# Gimbal_Controller_Board.net
KiCad netlist of a schematic drawn in EAGLE
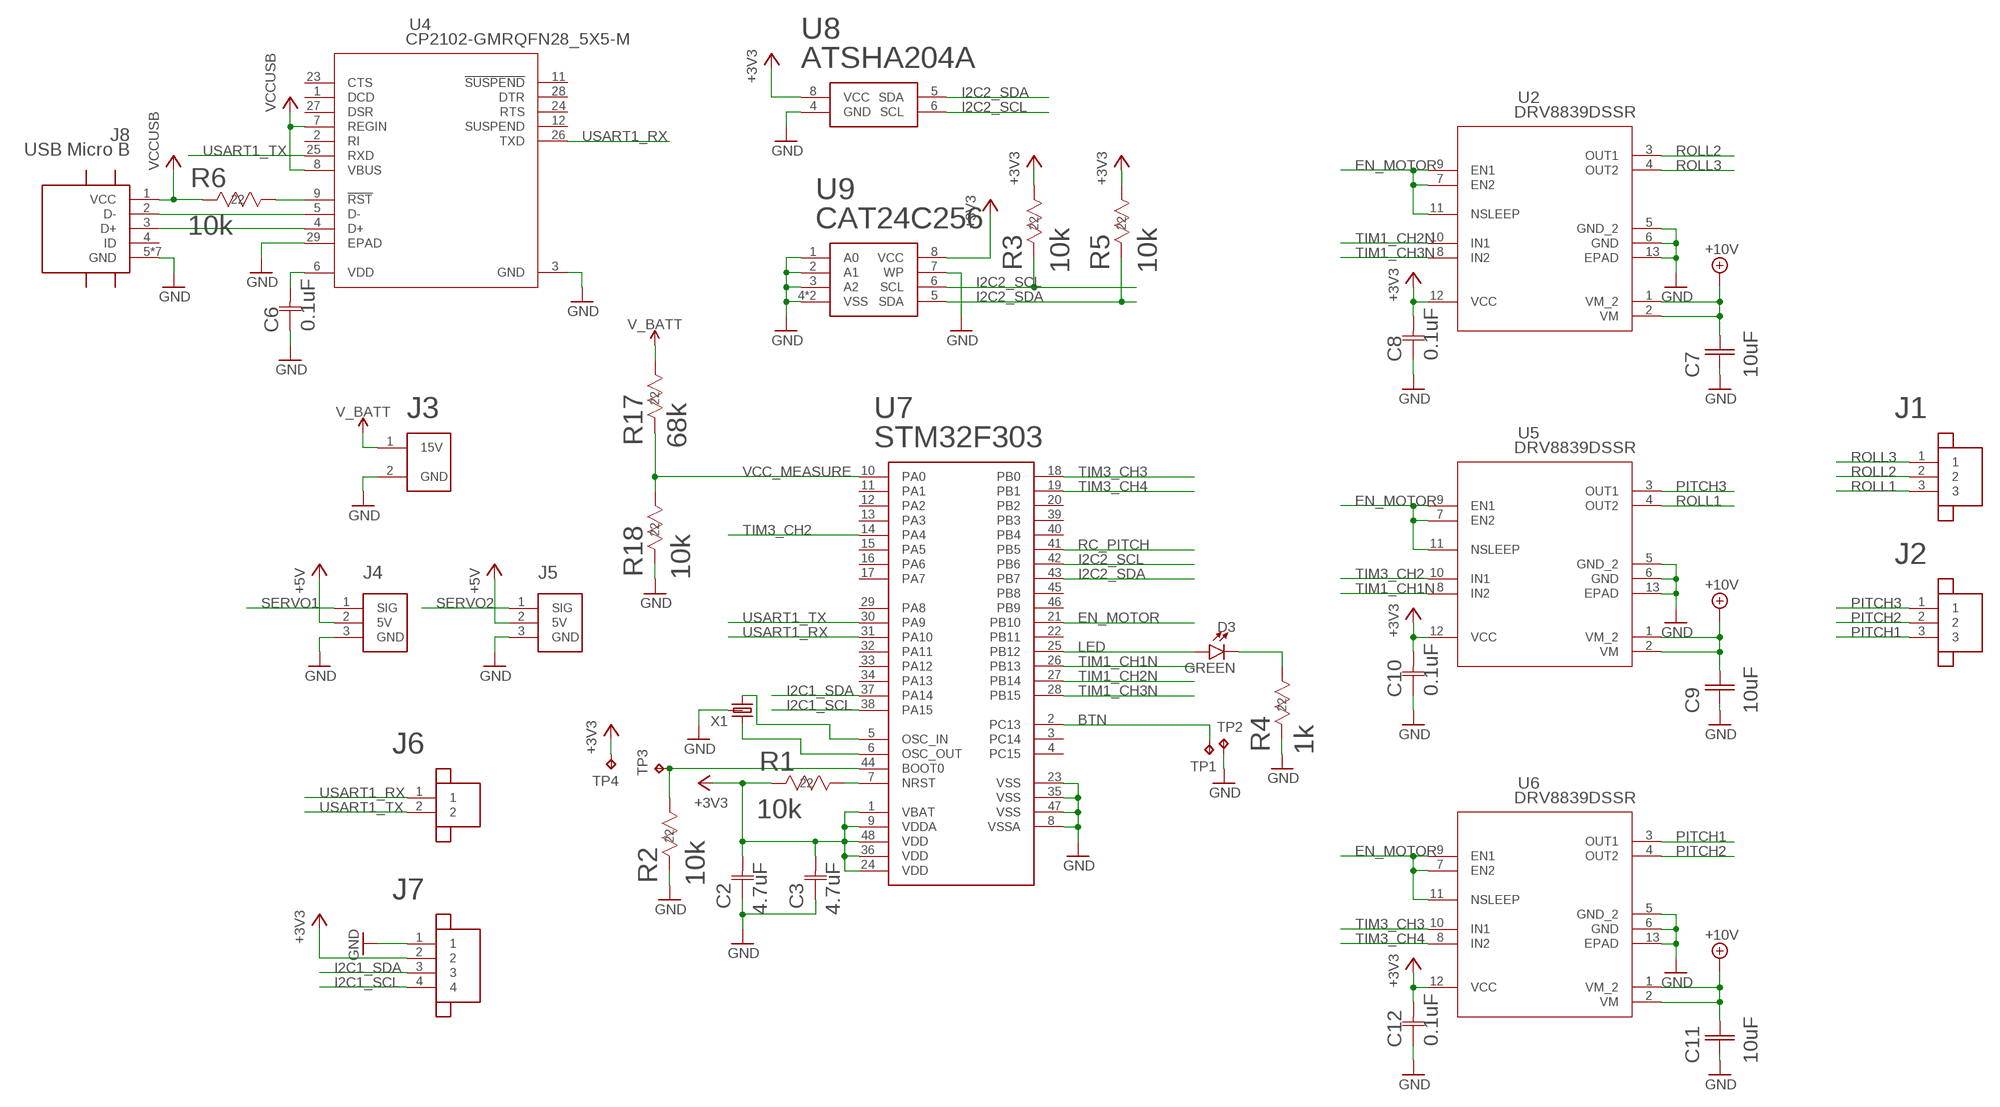
[diagram p0: schematic, sheet 1]
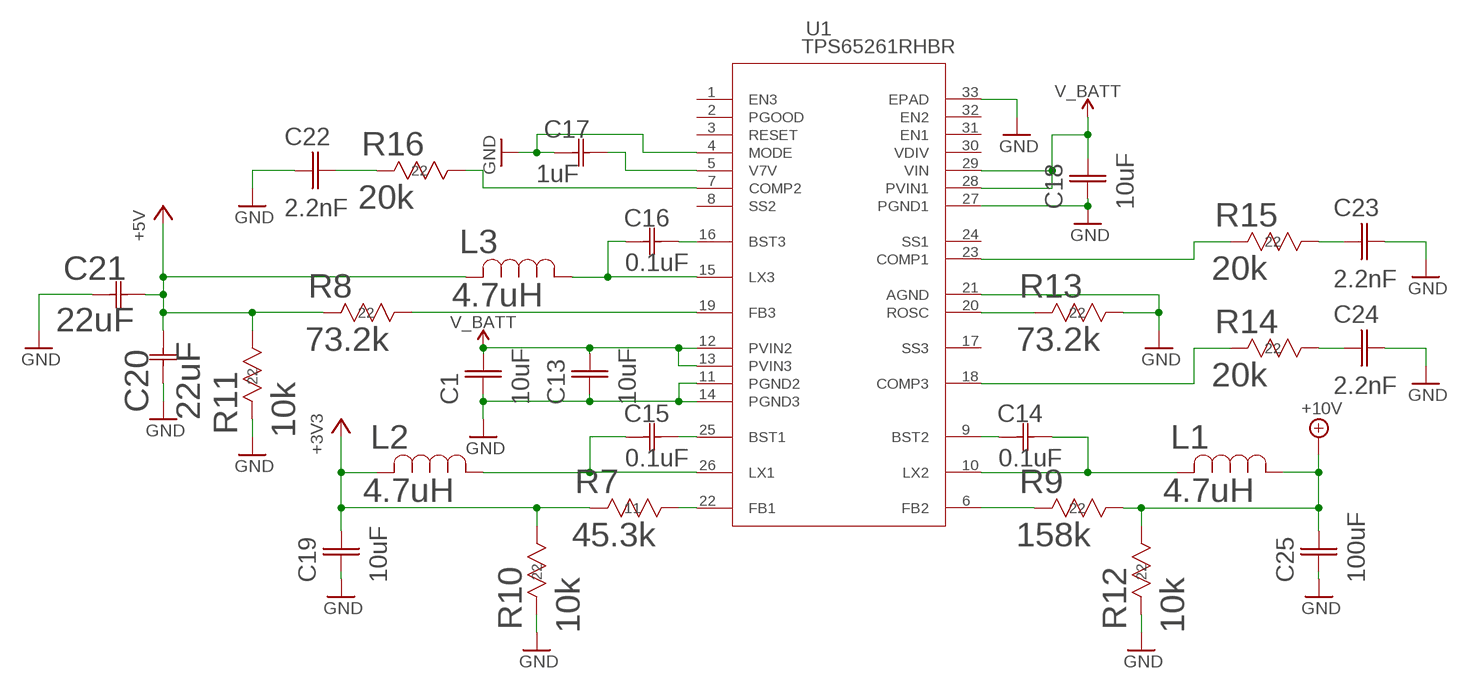
[diagram p1: schematic, sheet 2]

(export (version "E")
  (design (tool "Eeschema 10.0.6"))
  (components
    (comp (ref "C2")
      (value "4.7uF")
      (footprint "eagle-import:0603-M")
      (fields (field (name "MANUFACTURER_PART_NUMBER") "06036D475KAT2A"))
      (libsource (lib "eagle-import") (part "06036D475KAT2A0603-M"))
    )
    (comp (ref "C3")
      (value "4.7uF")
      (footprint "eagle-import:0603-M")
      (fields (field (name "MANUFACTURER_PART_NUMBER") "06036D475KAT2A"))
      (libsource (lib "eagle-import") (part "06036D475KAT2A0603-M"))
    )
    (comp (ref "C6")
      (value "0.1uF")
      (footprint "eagle-import:0402-M")
      (fields (field (name "MANUFACTURER_PART_NUMBER") "0402ZD104KAT2A"))
      (libsource (lib "eagle-import") (part "0402ZD104KAT2A0402-M"))
    )
    (comp (ref "C7")
      (value "10uF")
      (footprint "eagle-import:0805_CAPACITOR")
      (libsource (lib "eagle-import") (part "10UF_CAPACITOR"))
    )
    (comp (ref "C8")
      (value "0.1uF")
      (footprint "eagle-import:0402-M")
      (fields (field (name "MANUFACTURER_PART_NUMBER") "0402ZD104KAT2A"))
      (libsource (lib "eagle-import") (part "0402ZD104KAT2A0402-M"))
    )
    (comp (ref "C9")
      (value "10uF")
      (footprint "eagle-import:0805_CAPACITOR")
      (libsource (lib "eagle-import") (part "10UF_CAPACITOR"))
    )
    (comp (ref "C10")
      (value "0.1uF")
      (footprint "eagle-import:0402-M")
      (fields (field (name "MANUFACTURER_PART_NUMBER") "0402ZD104KAT2A"))
      (libsource (lib "eagle-import") (part "0402ZD104KAT2A0402-M"))
    )
    (comp (ref "C11")
      (value "10uF")
      (footprint "eagle-import:0805_CAPACITOR")
      (libsource (lib "eagle-import") (part "10UF_CAPACITOR"))
    )
    (comp (ref "C12")
      (value "0.1uF")
      (footprint "eagle-import:0402-M")
      (fields (field (name "MANUFACTURER_PART_NUMBER") "0402ZD104KAT2A"))
      (libsource (lib "eagle-import") (part "0402ZD104KAT2A0402-M"))
    )
    (comp (ref "D3")
      (value "GREEN")
      (footprint "eagle-import:LED-0603")
      (libsource (lib "eagle-import") (part "LED-GREEN0603"))
    )
    (comp (ref "J1")
      (value "JST_SH_3POS")
      (footprint "eagle-import:JST_SH_3POS")
      (libsource (lib "eagle-import") (part "JST_SH_3POS"))
    )
    (comp (ref "J2")
      (value "JST_SH_3POS")
      (footprint "eagle-import:JST_SH_3POS")
      (libsource (lib "eagle-import") (part "JST_SH_3POS"))
    )
    (comp (ref "J3")
      (value "GIMBAL_POWER_CONNECTOR")
      (footprint "eagle-import:XH_CONNECTOR")
      (libsource (lib "eagle-import") (part "GIMBAL_POWER_CONNECTOR"))
    )
    (comp (ref "J4")
      (value "SERVO_CONNECTOR")
      (footprint "eagle-import:SERVO_CONNECTOR")
      (libsource (lib "eagle-import") (part "SERVO_CONNECTOR"))
    )
    (comp (ref "J5")
      (value "SERVO_CONNECTOR")
      (footprint "eagle-import:SERVO_CONNECTOR")
      (libsource (lib "eagle-import") (part "SERVO_CONNECTOR"))
    )
    (comp (ref "J6")
      (value "JST_SH_2POS")
      (footprint "eagle-import:JST_SH_2POS")
      (libsource (lib "eagle-import") (part "JST_SH_2POS"))
    )
    (comp (ref "J7")
      (value "JST_SH_4POS")
      (footprint "eagle-import:JST_SH_4POS")
      (libsource (lib "eagle-import") (part "JST_SH_4POS"))
    )
    (comp (ref "J8")
      (value "USB_MICRO_B_SMT")
      (footprint "eagle-import:USB_MICRO_B_SMT")
      (libsource (lib "eagle-import") (part "USB_MICRO_B_SMT"))
    )
    (comp (ref "R1")
      (value "10k")
      (footprint "eagle-import:RC0805N")
      (fields
        (field (name "DIGIKEYPARTNUMBER") "P10KDATRND")
        (field (name "MANUFACTURER_PART_NUMBER") "ERA6AEB103V")
        (field (name "TOLERANCE") "0.1%")
        (field (name "COPYRIGHT") "Copyright C 2015 Accelerated Designs. All rights reserved")
      )
      (libsource (lib "eagle-import") (part "ERA-6AEB103V"))
    )
    (comp (ref "R2")
      (value "10k")
      (footprint "eagle-import:RC0805N")
      (fields
        (field (name "DIGIKEYPARTNUMBER") "P10KDATRND")
        (field (name "MANUFACTURER_PART_NUMBER") "ERA6AEB103V")
        (field (name "TOLERANCE") "0.1%")
        (field (name "COPYRIGHT") "Copyright C 2015 Accelerated Designs. All rights reserved")
      )
      (libsource (lib "eagle-import") (part "ERA-6AEB103V"))
    )
    (comp (ref "R3")
      (value "10k")
      (footprint "eagle-import:RC0805N")
      (fields
        (field (name "DIGIKEYPARTNUMBER") "P10KDATRND")
        (field (name "MANUFACTURER_PART_NUMBER") "ERA6AEB103V")
        (field (name "TOLERANCE") "0.1%")
        (field (name "COPYRIGHT") "Copyright C 2015 Accelerated Designs. All rights reserved")
      )
      (libsource (lib "eagle-import") (part "ERA-6AEB103V"))
    )
    (comp (ref "R4")
      (value "1k")
      (footprint "eagle-import:RC0603N-M")
      (fields
        (field (name "DIGIKEYPARTNUMBER") "3111.0KGRTRND")
        (field (name "MANUFACTURER_PART_NUMBER") "RC0603JR071KL")
        (field (name "NEWARKPARTNUMBER") "14M7231")
        (field (name "COPYRIGHT") "Copyright C 2015 Accelerated Designs. All rights reserved")
      )
      (libsource (lib "eagle-import") (part "RC0603JR-071KLRC0603N-M"))
    )
    (comp (ref "R5")
      (value "10k")
      (footprint "eagle-import:RC0805N")
      (fields
        (field (name "DIGIKEYPARTNUMBER") "P10KDATRND")
        (field (name "MANUFACTURER_PART_NUMBER") "ERA6AEB103V")
        (field (name "TOLERANCE") "0.1%")
        (field (name "COPYRIGHT") "Copyright C 2015 Accelerated Designs. All rights reserved")
      )
      (libsource (lib "eagle-import") (part "ERA-6AEB103V"))
    )
    (comp (ref "R6")
      (value "10k")
      (footprint "eagle-import:RC0805N")
      (fields
        (field (name "DIGIKEYPARTNUMBER") "P10KDATRND")
        (field (name "MANUFACTURER_PART_NUMBER") "ERA6AEB103V")
        (field (name "TOLERANCE") "0.1%")
        (field (name "COPYRIGHT") "Copyright C 2015 Accelerated Designs. All rights reserved")
      )
      (libsource (lib "eagle-import") (part "ERA-6AEB103V"))
    )
    (comp (ref "R17")
      (value "68k")
      (footprint "eagle-import:RC0402N-M")
      (fields (field (name "MANUFACTURER_PART_NUMBER") "RC0402FR0768KL"))
      (libsource (lib "eagle-import") (part "RC0402FR-0768KLRC0402N-M"))
    )
    (comp (ref "R18")
      (value "10k")
      (footprint "eagle-import:RC0805N")
      (fields
        (field (name "DIGIKEYPARTNUMBER") "P10KDATRND")
        (field (name "MANUFACTURER_PART_NUMBER") "ERA6AEB103V")
        (field (name "TOLERANCE") "0.1%")
        (field (name "COPYRIGHT") "Copyright C 2015 Accelerated Designs. All rights reserved")
      )
      (libsource (lib "eagle-import") (part "ERA-6AEB103V"))
    )
    (comp (ref "TP1")
      (value "TPB2,54")
      (footprint "eagle-import:B2,54")
      (libsource (lib "eagle-import") (part "TPB2,54"))
    )
    (comp (ref "TP2")
      (value "TPB2,54")
      (footprint "eagle-import:B2,54")
      (libsource (lib "eagle-import") (part "TPB2,54"))
    )
    (comp (ref "TP3")
      (value "TPB2,54")
      (footprint "eagle-import:B2,54")
      (libsource (lib "eagle-import") (part "TPB2,54"))
    )
    (comp (ref "TP4")
      (value "TPB2,54")
      (footprint "eagle-import:B2,54")
      (libsource (lib "eagle-import") (part "TPB2,54"))
    )
    (comp (ref "U2")
      (value "DRV8839DSSR")
      (footprint "eagle-import:DSS12_P9X2")
      (libsource (lib "eagle-import") (part "DRV8839DSSR"))
    )
    (comp (ref "U4")
      (value "CP2102-GMRQFN28_5X5-M")
      (footprint "eagle-import:QFN28_5X5-M")
      (fields (field (name "MANUFACTURER_PART_NUMBER") "CP2102GMR"))
      (libsource (lib "eagle-import") (part "CP2102-GMRQFN28_5X5-M"))
    )
    (comp (ref "U5")
      (value "DRV8839DSSR")
      (footprint "eagle-import:DSS12_P9X2")
      (libsource (lib "eagle-import") (part "DRV8839DSSR"))
    )
    (comp (ref "U6")
      (value "DRV8839DSSR")
      (footprint "eagle-import:DSS12_P9X2")
      (libsource (lib "eagle-import") (part "DRV8839DSSR"))
    )
    (comp (ref "U7")
      (value "STM32F303")
      (footprint "eagle-import:LQFP48")
      (libsource (lib "eagle-import") (part "STM32F303"))
    )
    (comp (ref "U8")
      (value "ATSHA204A")
      (footprint "eagle-import:UDFN8_3X2")
      (libsource (lib "eagle-import") (part "ATSHA204A"))
    )
    (comp (ref "U9")
      (value "CAT24C256")
      (footprint "eagle-import:UDFN8_3X2")
      (libsource (lib "eagle-import") (part "CAT24C256"))
    )
    (comp (ref "X1")
      (value "CSTCE8M00G55Z")
      (footprint "eagle-import:3-SMD")
      (libsource (lib "eagle-import") (part "CSTCE8M00G55Z"))
    )
    (comp (ref "C1")
      (value "10uF")
      (footprint "eagle-import:0805_CAPACITOR")
      (libsource (lib "eagle-import") (part "10UF_CAPACITOR"))
    )
    (comp (ref "C13")
      (value "10uF")
      (footprint "eagle-import:0805_CAPACITOR")
      (libsource (lib "eagle-import") (part "10UF_CAPACITOR"))
    )
    (comp (ref "C14")
      (value "0.1uF")
      (footprint "eagle-import:0402-M")
      (fields (field (name "MANUFACTURER_PART_NUMBER") "0402ZD104KAT2A"))
      (libsource (lib "eagle-import") (part "0402ZD104KAT2A0402-M"))
    )
    (comp (ref "C15")
      (value "0.1uF")
      (footprint "eagle-import:0402-M")
      (fields (field (name "MANUFACTURER_PART_NUMBER") "0402ZD104KAT2A"))
      (libsource (lib "eagle-import") (part "0402ZD104KAT2A0402-M"))
    )
    (comp (ref "C16")
      (value "0.1uF")
      (footprint "eagle-import:0402-M")
      (fields (field (name "MANUFACTURER_PART_NUMBER") "0402ZD104KAT2A"))
      (libsource (lib "eagle-import") (part "0402ZD104KAT2A0402-M"))
    )
    (comp (ref "C17")
      (value "1uF")
      (footprint "eagle-import:YAG_CC0805")
      (fields
        (field (name "MANUFACTURER_PART_NUMBER") "CC0805KKX7R7BB105")
        (field (name "COPYRIGHT") "Copyright C 2015 Accelerated Designs. All rights reserved")
      )
      (libsource (lib "eagle-import") (part "CC0805KKX7R7BB105"))
    )
    (comp (ref "C18")
      (value "10uF")
      (footprint "eagle-import:0805_CAPACITOR")
      (libsource (lib "eagle-import") (part "10UF_CAPACITOR"))
    )
    (comp (ref "C19")
      (value "10uF")
      (footprint "eagle-import:0805_CAPACITOR")
      (libsource (lib "eagle-import") (part "10UF_CAPACITOR"))
    )
    (comp (ref "C20")
      (value "22uF")
      (footprint "eagle-import:G-21")
      (fields
        (field (name "MANUFACTURER_PART_NUMBER") "GRM21BR60J226ME39L")
        (field (name "COPYRIGHT") "Copyright C 2015 Accelerated Designs. All rights reserved")
      )
      (libsource (lib "eagle-import") (part "GRM21BR60J226ME39L"))
    )
    (comp (ref "C21")
      (value "22uF")
      (footprint "eagle-import:G-21")
      (fields
        (field (name "MANUFACTURER_PART_NUMBER") "GRM21BR60J226ME39L")
        (field (name "COPYRIGHT") "Copyright C 2015 Accelerated Designs. All rights reserved")
      )
      (libsource (lib "eagle-import") (part "GRM21BR60J226ME39L"))
    )
    (comp (ref "C22")
      (value "2.2nF")
      (footprint "eagle-import:0402_CAPACITOR")
      (libsource (lib "eagle-import") (part "2200PF_CAPACITOR"))
    )
    (comp (ref "C23")
      (value "2.2nF")
      (footprint "eagle-import:0402_CAPACITOR")
      (libsource (lib "eagle-import") (part "2200PF_CAPACITOR"))
    )
    (comp (ref "C24")
      (value "2.2nF")
      (footprint "eagle-import:0402_CAPACITOR")
      (libsource (lib "eagle-import") (part "2200PF_CAPACITOR"))
    )
    (comp (ref "C25")
      (value "100uF")
      (footprint "eagle-import:1210_CAPACITOR")
      (libsource (lib "eagle-import") (part "100UF_CER_CAPACITOR"))
    )
    (comp (ref "L1")
      (value "4.7uH")
      (footprint "eagle-import:1008")
      (libsource (lib "eagle-import") (part "DFE252012P-4R7M=P2{dblquote}"))
    )
    (comp (ref "L2")
      (value "4.7uH")
      (footprint "eagle-import:1008")
      (libsource (lib "eagle-import") (part "DFE252012P-4R7M=P2{dblquote}"))
    )
    (comp (ref "L3")
      (value "4.7uH")
      (footprint "eagle-import:1008")
      (libsource (lib "eagle-import") (part "DFE252012P-4R7M=P2{dblquote}"))
    )
    (comp (ref "R7")
      (value "45.3k")
      (footprint "eagle-import:STA_RMCF0402-M")
      (fields (field (name "MANUFACTURER_PART_NUMBER") "RMCF0402FT73K2"))
      (libsource (lib "eagle-import") (part "RMCF0402FT73K2STA_RMCF0402-M"))
    )
    (comp (ref "R8")
      (value "73.2k")
      (footprint "eagle-import:RC0402N-M")
      (fields (field (name "MANUFACTURER_PART_NUMBER") "RC0402FR0745K3L"))
      (libsource (lib "eagle-import") (part "RC0402FR-0745K3LRC0402N-M"))
    )
    (comp (ref "R9")
      (value "158k")
      (footprint "eagle-import:RC0402N-M")
      (fields (field (name "MANUFACTURER_PART_NUMBER") "RC0402FR07150KL"))
      (libsource (lib "eagle-import") (part "RC0402FR-07150KLRC0402N-M"))
    )
    (comp (ref "R10")
      (value "10k")
      (footprint "eagle-import:RC0805N")
      (fields
        (field (name "DIGIKEYPARTNUMBER") "P10KDATRND")
        (field (name "MANUFACTURER_PART_NUMBER") "ERA6AEB103V")
        (field (name "TOLERANCE") "0.1%")
        (field (name "COPYRIGHT") "Copyright C 2015 Accelerated Designs. All rights reserved")
      )
      (libsource (lib "eagle-import") (part "ERA-6AEB103V"))
    )
    (comp (ref "R11")
      (value "10k")
      (footprint "eagle-import:RC0805N")
      (fields
        (field (name "DIGIKEYPARTNUMBER") "P10KDATRND")
        (field (name "MANUFACTURER_PART_NUMBER") "ERA6AEB103V")
        (field (name "TOLERANCE") "0.1%")
        (field (name "COPYRIGHT") "Copyright C 2015 Accelerated Designs. All rights reserved")
      )
      (libsource (lib "eagle-import") (part "ERA-6AEB103V"))
    )
    (comp (ref "R12")
      (value "10k")
      (footprint "eagle-import:RC0805N")
      (fields
        (field (name "DIGIKEYPARTNUMBER") "P10KDATRND")
        (field (name "MANUFACTURER_PART_NUMBER") "ERA6AEB103V")
        (field (name "TOLERANCE") "0.1%")
        (field (name "COPYRIGHT") "Copyright C 2015 Accelerated Designs. All rights reserved")
      )
      (libsource (lib "eagle-import") (part "ERA-6AEB103V"))
    )
    (comp (ref "R13")
      (value "73.2k")
      (footprint "eagle-import:RC0402N-M")
      (fields (field (name "MANUFACTURER_PART_NUMBER") "RC0402FR0745K3L"))
      (libsource (lib "eagle-import") (part "RC0402FR-0745K3LRC0402N-M"))
    )
    (comp (ref "R14")
      (value "20k")
      (footprint "eagle-import:RC0402N-M")
      (fields (field (name "MANUFACTURER_PART_NUMBER") "RC0402FR0720KL"))
      (libsource (lib "eagle-import") (part "RC0402FR-0720KLRC0402N-M"))
    )
    (comp (ref "R15")
      (value "20k")
      (footprint "eagle-import:RC0402N-M")
      (fields (field (name "MANUFACTURER_PART_NUMBER") "RC0402FR0720KL"))
      (libsource (lib "eagle-import") (part "RC0402FR-0720KLRC0402N-M"))
    )
    (comp (ref "R16")
      (value "20k")
      (footprint "eagle-import:RC0402N-M")
      (fields (field (name "MANUFACTURER_PART_NUMBER") "RC0402FR0720KL"))
      (libsource (lib "eagle-import") (part "RC0402FR-0720KLRC0402N-M"))
    )
    (comp (ref "U1")
      (value "TPS65261RHBR")
      (footprint "eagle-import:RHB32_3P45X3P45")
      (libsource (lib "eagle-import") (part "TPS65261RHBR"))
    )
  )
  (nets
    (net (code "1") (name "+3V3") (class "Default")
      (node (ref "C10") (pin "2") (pinfunction "2_2") (pintype "passive"))
      (node (ref "C12") (pin "2") (pinfunction "2_2") (pintype "passive"))
      (node (ref "C19") (pin "2") (pinfunction "2_2") (pintype "bidirectional"))
      (node (ref "C2") (pin "2") (pinfunction "2_2") (pintype "passive"))
      (node (ref "C3") (pin "2") (pinfunction "2_2") (pintype "passive"))
      (node (ref "C8") (pin "2") (pinfunction "2_2") (pintype "passive"))
      (node (ref "J7") (pin "2") (pinfunction "2_2") (pintype "bidirectional"))
      (node (ref "L2") (pin "P$2") (pinfunction "2_P$2") (pintype "passive"))
      (node (ref "R1") (pin "2") (pinfunction "22_2") (pintype "passive"))
      (node (ref "R10") (pin "1") (pinfunction "11_1") (pintype "passive"))
      (node (ref "R3") (pin "1") (pinfunction "11_1") (pintype "passive"))
      (node (ref "R5") (pin "1") (pinfunction "11_1") (pintype "passive"))
      (node (ref "R7") (pin "1") (pinfunction "11_1") (pintype "passive"))
      (node (ref "TP4") (pin "TP") (pinfunction "TP_TP") (pintype "input"))
      (node (ref "U2") (pin "12") (pinfunction "VCC_12") (pintype "power_in"))
      (node (ref "U5") (pin "12") (pinfunction "VCC_12") (pintype "power_in"))
      (node (ref "U6") (pin "12") (pinfunction "VCC_12") (pintype "power_in"))
      (node (ref "U7") (pin "1") (pinfunction "VBAT_1") (pintype "bidirectional"))
      (node (ref "U7") (pin "24") (pinfunction "VDD_24") (pintype "bidirectional"))
      (node (ref "U7") (pin "36") (pinfunction "VDD_36") (pintype "bidirectional"))
      (node (ref "U7") (pin "48") (pinfunction "VDD_48") (pintype "bidirectional"))
      (node (ref "U7") (pin "9") (pinfunction "VDDA_9") (pintype "bidirectional"))
      (node (ref "U8") (pin "8") (pinfunction "VCC_8") (pintype "bidirectional"))
      (node (ref "U9") (pin "8") (pinfunction "VCC_8") (pintype "bidirectional"))
    )
    (net (code "2") (name "+5V") (class "Default")
      (node (ref "C20") (pin "2") (pinfunction "22_2") (pintype "passive"))
      (node (ref "C21") (pin "2") (pinfunction "22_2") (pintype "passive"))
      (node (ref "J4") (pin "2") (pinfunction "5V_2") (pintype "power_in"))
      (node (ref "J5") (pin "2") (pinfunction "5V_2") (pintype "power_in"))
      (node (ref "L3") (pin "P$2") (pinfunction "2_P$2") (pintype "passive"))
      (node (ref "R11") (pin "1") (pinfunction "11_1") (pintype "passive"))
      (node (ref "R8") (pin "2") (pinfunction "22_2") (pintype "passive"))
    )
    (net (code "3") (name "+10V") (class "Default")
      (node (ref "C11") (pin "2") (pinfunction "2_2") (pintype "bidirectional"))
      (node (ref "C25") (pin "2") (pinfunction "2_2") (pintype "bidirectional"))
      (node (ref "C7") (pin "2") (pinfunction "2_2") (pintype "bidirectional"))
      (node (ref "C9") (pin "2") (pinfunction "2_2") (pintype "bidirectional"))
      (node (ref "L1") (pin "P$1") (pinfunction "1_P$1") (pintype "passive"))
      (node (ref "R12") (pin "1") (pinfunction "11_1") (pintype "passive"))
      (node (ref "R9") (pin "1") (pinfunction "11_1") (pintype "passive"))
      (node (ref "U2") (pin "1") (pinfunction "VM_2_1") (pintype "power_in"))
      (node (ref "U2") (pin "2") (pinfunction "VM_2") (pintype "power_in"))
      (node (ref "U5") (pin "1") (pinfunction "VM_2_1") (pintype "power_in"))
      (node (ref "U5") (pin "2") (pinfunction "VM_2") (pintype "power_in"))
      (node (ref "U6") (pin "1") (pinfunction "VM_2_1") (pintype "power_in"))
      (node (ref "U6") (pin "2") (pinfunction "VM_2") (pintype "power_in"))
    )
    (net (code "4") (name "BTN") (class "Default")
      (node (ref "TP1") (pin "TP") (pinfunction "TP_TP") (pintype "input"))
      (node (ref "U7") (pin "2") (pinfunction "PC13_2") (pintype "bidirectional"))
    )
    (net (code "5") (name "EN_MOTOR") (class "Default")
      (node (ref "U2") (pin "11") (pinfunction "NSLEEP_11") (pintype "input"))
      (node (ref "U2") (pin "7") (pinfunction "EN2_7") (pintype "input"))
      (node (ref "U2") (pin "9") (pinfunction "EN1_9") (pintype "input"))
      (node (ref "U5") (pin "11") (pinfunction "NSLEEP_11") (pintype "input"))
      (node (ref "U5") (pin "7") (pinfunction "EN2_7") (pintype "input"))
      (node (ref "U5") (pin "9") (pinfunction "EN1_9") (pintype "input"))
      (node (ref "U6") (pin "11") (pinfunction "NSLEEP_11") (pintype "input"))
      (node (ref "U6") (pin "7") (pinfunction "EN2_7") (pintype "input"))
      (node (ref "U6") (pin "9") (pinfunction "EN1_9") (pintype "input"))
      (node (ref "U7") (pin "21") (pinfunction "PB10_21") (pintype "bidirectional"))
    )
    (net (code "6") (name "GND") (class "Default")
      (node (ref "C1") (pin "1") (pinfunction "1_1") (pintype "bidirectional"))
      (node (ref "C10") (pin "1") (pinfunction "1_1") (pintype "passive"))
      (node (ref "C11") (pin "1") (pinfunction "1_1") (pintype "bidirectional"))
      (node (ref "C12") (pin "1") (pinfunction "1_1") (pintype "passive"))
      (node (ref "C13") (pin "1") (pinfunction "1_1") (pintype "bidirectional"))
      (node (ref "C17") (pin "1") (pinfunction "11_1") (pintype "passive"))
      (node (ref "C18") (pin "1") (pinfunction "1_1") (pintype "bidirectional"))
      (node (ref "C19") (pin "1") (pinfunction "1_1") (pintype "bidirectional"))
      (node (ref "C2") (pin "1") (pinfunction "1_1") (pintype "passive"))
      (node (ref "C20") (pin "1") (pinfunction "11_1") (pintype "passive"))
      (node (ref "C21") (pin "1") (pinfunction "11_1") (pintype "passive"))
      (node (ref "C22") (pin "1") (pinfunction "1_1") (pintype "bidirectional"))
      (node (ref "C23") (pin "2") (pinfunction "2_2") (pintype "bidirectional"))
      (node (ref "C24") (pin "2") (pinfunction "2_2") (pintype "bidirectional"))
      (node (ref "C25") (pin "1") (pinfunction "1_1") (pintype "bidirectional"))
      (node (ref "C3") (pin "1") (pinfunction "1_1") (pintype "passive"))
      (node (ref "C6") (pin "1") (pinfunction "1_1") (pintype "passive"))
      (node (ref "C7") (pin "1") (pinfunction "1_1") (pintype "bidirectional"))
      (node (ref "C8") (pin "1") (pinfunction "1_1") (pintype "passive"))
      (node (ref "C9") (pin "1") (pinfunction "1_1") (pintype "bidirectional"))
      (node (ref "J3") (pin "2") (pinfunction "GND_2") (pintype "power_in"))
      (node (ref "J4") (pin "3") (pinfunction "GND_3") (pintype "power_in"))
      (node (ref "J5") (pin "3") (pinfunction "GND_3") (pintype "power_in"))
      (node (ref "J7") (pin "1") (pinfunction "1_1") (pintype "bidirectional"))
      (node (ref "J8") (pin "5") (pinfunction "GND_5") (pintype "power_in"))
      (node (ref "J8") (pin "6") (pinfunction "GND_6") (pintype "power_in"))
      (node (ref "J8") (pin "7") (pinfunction "GND_7") (pintype "power_in"))
      (node (ref "J8") (pin "P$1") (pinfunction "GND_P$1") (pintype "power_in"))
      (node (ref "J8") (pin "P$2") (pinfunction "GND_P$2") (pintype "power_in"))
      (node (ref "J8") (pin "P$3") (pinfunction "GND_P$3") (pintype "power_in"))
      (node (ref "J8") (pin "P$4") (pinfunction "GND_P$4") (pintype "power_in"))
      (node (ref "R10") (pin "2") (pinfunction "22_2") (pintype "passive"))
      (node (ref "R11") (pin "2") (pinfunction "22_2") (pintype "passive"))
      (node (ref "R12") (pin "2") (pinfunction "22_2") (pintype "passive"))
      (node (ref "R13") (pin "1") (pinfunction "11_1") (pintype "passive"))
      (node (ref "R18") (pin "2") (pinfunction "22_2") (pintype "passive"))
      (node (ref "R2") (pin "2") (pinfunction "22_2") (pintype "passive"))
      (node (ref "R4") (pin "2") (pinfunction "22_2") (pintype "passive"))
      (node (ref "TP2") (pin "TP") (pinfunction "TP_TP") (pintype "input"))
      (node (ref "U1") (pin "11") (pinfunction "PGND2_11") (pintype "power_in"))
      (node (ref "U1") (pin "14") (pinfunction "PGND3_14") (pintype "power_in"))
      (node (ref "U1") (pin "21") (pinfunction "AGND_21") (pintype "power_in"))
      (node (ref "U1") (pin "27") (pinfunction "PGND1_27") (pintype "power_in"))
      (node (ref "U1") (pin "33") (pinfunction "EPAD_33") (pintype "passive"))
      (node (ref "U1") (pin "4") (pinfunction "MODE_4") (pintype "passive"))
      (node (ref "U2") (pin "13") (pinfunction "EPAD_13") (pintype "passive"))
      (node (ref "U2") (pin "5") (pinfunction "GND_2_5") (pintype "power_in"))
      (node (ref "U2") (pin "6") (pinfunction "GND_6") (pintype "power_in"))
      (node (ref "U4") (pin "29") (pinfunction "EPAD_29") (pintype "passive"))
      (node (ref "U4") (pin "3") (pinfunction "GND_3") (pintype "power_in"))
      (node (ref "U5") (pin "13") (pinfunction "EPAD_13") (pintype "passive"))
      (node (ref "U5") (pin "5") (pinfunction "GND_2_5") (pintype "power_in"))
      (node (ref "U5") (pin "6") (pinfunction "GND_6") (pintype "power_in"))
      (node (ref "U6") (pin "13") (pinfunction "EPAD_13") (pintype "passive"))
      (node (ref "U6") (pin "5") (pinfunction "GND_2_5") (pintype "power_in"))
      (node (ref "U6") (pin "6") (pinfunction "GND_6") (pintype "power_in"))
      (node (ref "U7") (pin "23") (pinfunction "VSS_23") (pintype "bidirectional"))
      (node (ref "U7") (pin "35") (pinfunction "VSS_35") (pintype "bidirectional"))
      (node (ref "U7") (pin "47") (pinfunction "VSS_47") (pintype "bidirectional"))
      (node (ref "U7") (pin "8") (pinfunction "VSSA_8") (pintype "bidirectional"))
      (node (ref "U8") (pin "4") (pinfunction "GND_4") (pintype "bidirectional"))
      (node (ref "U9") (pin "1") (pinfunction "A0_1") (pintype "bidirectional"))
      (node (ref "U9") (pin "2") (pinfunction "A1_2") (pintype "bidirectional"))
      (node (ref "U9") (pin "3") (pinfunction "A2_3") (pintype "bidirectional"))
      (node (ref "U9") (pin "4") (pinfunction "VSS_4") (pintype "bidirectional"))
      (node (ref "U9") (pin "7") (pinfunction "WP_7") (pintype "bidirectional"))
      (node (ref "U9") (pin "9") (pinfunction "VSS_9") (pintype "bidirectional"))
      (node (ref "X1") (pin "2") (pinfunction "GND_2") (pintype "bidirectional"))
    )
    (net (code "7") (name "I2C1_SCL") (class "Default")
      (node (ref "J7") (pin "4") (pinfunction "4_4") (pintype "bidirectional"))
      (node (ref "U7") (pin "38") (pinfunction "PA15_38") (pintype "bidirectional"))
    )
    (net (code "8") (name "I2C1_SDA") (class "Default")
      (node (ref "J7") (pin "3") (pinfunction "3_3") (pintype "bidirectional"))
      (node (ref "U7") (pin "37") (pinfunction "PA14_37") (pintype "bidirectional"))
    )
    (net (code "9") (name "I2C2_SCL") (class "Default")
      (node (ref "R3") (pin "2") (pinfunction "22_2") (pintype "passive"))
      (node (ref "U7") (pin "42") (pinfunction "PB6_42") (pintype "bidirectional"))
      (node (ref "U8") (pin "6") (pinfunction "SCL_6") (pintype "bidirectional"))
      (node (ref "U9") (pin "6") (pinfunction "SCL_6") (pintype "bidirectional"))
    )
    (net (code "10") (name "I2C2_SDA") (class "Default")
      (node (ref "R5") (pin "2") (pinfunction "22_2") (pintype "passive"))
      (node (ref "U7") (pin "43") (pinfunction "PB7_43") (pintype "bidirectional"))
      (node (ref "U8") (pin "5") (pinfunction "SDA_5") (pintype "bidirectional"))
      (node (ref "U9") (pin "5") (pinfunction "SDA_5") (pintype "bidirectional"))
    )
    (net (code "11") (name "LED") (class "Default")
      (node (ref "D3") (pin "A") (pinfunction "A_A") (pintype "passive"))
      (node (ref "U7") (pin "25") (pinfunction "PB12_25") (pintype "bidirectional"))
    )
    (net (code "12") (name "Net-(C17-22)") (class "Default")
      (node (ref "C17") (pin "2") (pinfunction "22_2") (pintype "passive"))
      (node (ref "U1") (pin "5") (pinfunction "V7V_5") (pintype "power_in"))
    )
    (net (code "13") (name "Net-(J8-D+)") (class "Default")
      (node (ref "J8") (pin "3") (pinfunction "D+_3") (pintype "bidirectional"))
      (node (ref "U4") (pin "4") (pinfunction "D+_4") (pintype "bidirectional"))
    )
    (net (code "14") (name "Net-(J8-D-)") (class "Default")
      (node (ref "J8") (pin "2") (pinfunction "D-_2") (pintype "bidirectional"))
      (node (ref "U4") (pin "5") (pinfunction "D-_5") (pintype "bidirectional"))
    )
    (net (code "15") (name "Net-(L1-2)") (class "Default")
      (node (ref "C14") (pin "2") (pinfunction "2_2") (pintype "passive"))
      (node (ref "L1") (pin "P$2") (pinfunction "2_P$2") (pintype "passive"))
      (node (ref "U1") (pin "10") (pinfunction "LX2_10") (pintype "passive"))
    )
    (net (code "16") (name "Net-(L2-1)") (class "Default")
      (node (ref "C15") (pin "1") (pinfunction "1_1") (pintype "passive"))
      (node (ref "L2") (pin "P$1") (pinfunction "1_P$1") (pintype "passive"))
      (node (ref "U1") (pin "26") (pinfunction "LX1_26") (pintype "passive"))
    )
    (net (code "17") (name "Net-(L3-1)") (class "Default")
      (node (ref "C16") (pin "1") (pinfunction "1_1") (pintype "passive"))
      (node (ref "L3") (pin "P$1") (pinfunction "1_P$1") (pintype "passive"))
      (node (ref "U1") (pin "15") (pinfunction "LX3_15") (pintype "passive"))
    )
    (net (code "18") (name "Net-(R1-11)") (class "Default")
      (node (ref "R1") (pin "1") (pinfunction "11_1") (pintype "passive"))
      (node (ref "U7") (pin "7") (pinfunction "NRST_7") (pintype "bidirectional"))
    )
    (net (code "19") (name "Net-(R2-11)") (class "Default")
      (node (ref "R2") (pin "1") (pinfunction "11_1") (pintype "passive"))
      (node (ref "TP3") (pin "TP") (pinfunction "TP_TP") (pintype "input"))
      (node (ref "U7") (pin "44") (pinfunction "BOOT0_44") (pintype "bidirectional"))
    )
    (net (code "20") (name "Net-(R4-11)") (class "Default")
      (node (ref "D3") (pin "C") (pinfunction "C_C") (pintype "passive"))
      (node (ref "R4") (pin "1") (pinfunction "11_1") (pintype "passive"))
    )
    (net (code "21") (name "Net-(R6-11)") (class "Default")
      (node (ref "R6") (pin "1") (pinfunction "11_1") (pintype "passive"))
      (node (ref "U4") (pin "9") (pinfunction "~{RST}_9") (pintype "bidirectional"))
    )
    (net (code "22") (name "Net-(R7-22)") (class "Default")
      (node (ref "R7") (pin "2") (pinfunction "22_2") (pintype "passive"))
      (node (ref "U1") (pin "22") (pinfunction "FB1_22") (pintype "output"))
    )
    (net (code "23") (name "Net-(R8-11)") (class "Default")
      (node (ref "R8") (pin "1") (pinfunction "11_1") (pintype "passive"))
      (node (ref "U1") (pin "19") (pinfunction "FB3_19") (pintype "output"))
    )
    (net (code "24") (name "Net-(R9-22)") (class "Default")
      (node (ref "R9") (pin "2") (pinfunction "22_2") (pintype "passive"))
      (node (ref "U1") (pin "6") (pinfunction "FB2_6") (pintype "output"))
    )
    (net (code "25") (name "Net-(R13-22)") (class "Default")
      (node (ref "R13") (pin "2") (pinfunction "22_2") (pintype "passive"))
      (node (ref "U1") (pin "20") (pinfunction "ROSC_20") (pintype "passive"))
    )
    (net (code "26") (name "Net-(R14-11)") (class "Default")
      (node (ref "C24") (pin "1") (pinfunction "1_1") (pintype "bidirectional"))
      (node (ref "R14") (pin "1") (pinfunction "11_1") (pintype "passive"))
    )
    (net (code "27") (name "Net-(R14-22)") (class "Default")
      (node (ref "R14") (pin "2") (pinfunction "22_2") (pintype "passive"))
      (node (ref "U1") (pin "18") (pinfunction "COMP3_18") (pintype "output"))
    )
    (net (code "28") (name "Net-(R15-11)") (class "Default")
      (node (ref "C23") (pin "1") (pinfunction "1_1") (pintype "bidirectional"))
      (node (ref "R15") (pin "1") (pinfunction "11_1") (pintype "passive"))
    )
    (net (code "29") (name "Net-(R15-22)") (class "Default")
      (node (ref "R15") (pin "2") (pinfunction "22_2") (pintype "passive"))
      (node (ref "U1") (pin "23") (pinfunction "COMP1_23") (pintype "output"))
    )
    (net (code "30") (name "Net-(R16-11)") (class "Default")
      (node (ref "R16") (pin "1") (pinfunction "11_1") (pintype "passive"))
      (node (ref "U1") (pin "7") (pinfunction "COMP2_7") (pintype "output"))
    )
    (net (code "31") (name "Net-(R16-22)") (class "Default")
      (node (ref "C22") (pin "2") (pinfunction "2_2") (pintype "bidirectional"))
      (node (ref "R16") (pin "2") (pinfunction "22_2") (pintype "passive"))
    )
    (net (code "32") (name "Net-(U1-BST1)") (class "Default")
      (node (ref "C15") (pin "2") (pinfunction "2_2") (pintype "passive"))
      (node (ref "U1") (pin "25") (pinfunction "BST1_25") (pintype "passive"))
    )
    (net (code "33") (name "Net-(U1-BST2)") (class "Default")
      (node (ref "C14") (pin "1") (pinfunction "1_1") (pintype "passive"))
      (node (ref "U1") (pin "9") (pinfunction "BST2_9") (pintype "passive"))
    )
    (net (code "34") (name "Net-(U1-BST3)") (class "Default")
      (node (ref "C16") (pin "2") (pinfunction "2_2") (pintype "passive"))
      (node (ref "U1") (pin "16") (pinfunction "BST3_16") (pintype "passive"))
    )
    (net (code "35") (name "Net-(U4-VDD)") (class "Default")
      (node (ref "C6") (pin "2") (pinfunction "2_2") (pintype "passive"))
      (node (ref "U4") (pin "6") (pinfunction "VDD_6") (pintype "power_in"))
    )
    (net (code "36") (name "Net-(U7-OSC_IN)") (class "Default")
      (node (ref "U7") (pin "5") (pinfunction "OSC_IN_5") (pintype "bidirectional"))
      (node (ref "X1") (pin "3") (pinfunction "2_3") (pintype "passive"))
    )
    (net (code "37") (name "Net-(U7-OSC_OUT)") (class "Default")
      (node (ref "U7") (pin "6") (pinfunction "OSC_OUT_6") (pintype "bidirectional"))
      (node (ref "X1") (pin "1") (pinfunction "1_1") (pintype "passive"))
    )
    (net (code "38") (name "P$1") (class "Default")
      (node (ref "J8") (pin "1") (pinfunction "VCC_1") (pintype "power_in"))
      (node (ref "R6") (pin "2") (pinfunction "22_2") (pintype "passive"))
      (node (ref "U4") (pin "7") (pinfunction "REGIN_7") (pintype "input"))
      (node (ref "U4") (pin "8") (pinfunction "VBUS_8") (pintype "input"))
    )
    (net (code "39") (name "PITCH1") (class "Default")
      (node (ref "J2") (pin "3") (pinfunction "3_3") (pintype "bidirectional"))
      (node (ref "U6") (pin "3") (pinfunction "OUT1_3") (pintype "output"))
    )
    (net (code "40") (name "PITCH2") (class "Default")
      (node (ref "J2") (pin "2") (pinfunction "2_2") (pintype "bidirectional"))
      (node (ref "U6") (pin "4") (pinfunction "OUT2_4") (pintype "output"))
    )
    (net (code "41") (name "PITCH3") (class "Default")
      (node (ref "J2") (pin "1") (pinfunction "1_1") (pintype "bidirectional"))
      (node (ref "U5") (pin "3") (pinfunction "OUT1_3") (pintype "output"))
    )
    (net (code "42") (name "RC_PITCH") (class "Default")
      (node (ref "U7") (pin "41") (pinfunction "PB5_41") (pintype "bidirectional"))
    )
    (net (code "43") (name "ROLL1") (class "Default")
      (node (ref "J1") (pin "3") (pinfunction "3_3") (pintype "bidirectional"))
      (node (ref "U5") (pin "4") (pinfunction "OUT2_4") (pintype "output"))
    )
    (net (code "44") (name "ROLL2") (class "Default")
      (node (ref "J1") (pin "2") (pinfunction "2_2") (pintype "bidirectional"))
      (node (ref "U2") (pin "3") (pinfunction "OUT1_3") (pintype "output"))
    )
    (net (code "45") (name "ROLL3") (class "Default")
      (node (ref "J1") (pin "1") (pinfunction "1_1") (pintype "bidirectional"))
      (node (ref "U2") (pin "4") (pinfunction "OUT2_4") (pintype "output"))
    )
    (net (code "46") (name "SERVO1") (class "Default")
      (node (ref "J4") (pin "1") (pinfunction "SIG_1") (pintype "bidirectional"))
    )
    (net (code "47") (name "SERVO2") (class "Default")
      (node (ref "J5") (pin "1") (pinfunction "SIG_1") (pintype "bidirectional"))
    )
    (net (code "48") (name "TIM1_CH1N") (class "Default")
      (node (ref "U5") (pin "8") (pinfunction "IN2_8") (pintype "input"))
      (node (ref "U7") (pin "26") (pinfunction "PB13_26") (pintype "bidirectional"))
    )
    (net (code "49") (name "TIM1_CH2N") (class "Default")
      (node (ref "U2") (pin "10") (pinfunction "IN1_10") (pintype "input"))
      (node (ref "U7") (pin "27") (pinfunction "PB14_27") (pintype "bidirectional"))
    )
    (net (code "50") (name "TIM1_CH3N") (class "Default")
      (node (ref "U2") (pin "8") (pinfunction "IN2_8") (pintype "input"))
      (node (ref "U7") (pin "28") (pinfunction "PB15_28") (pintype "bidirectional"))
    )
    (net (code "51") (name "TIM3_CH2") (class "Default")
      (node (ref "U5") (pin "10") (pinfunction "IN1_10") (pintype "input"))
      (node (ref "U7") (pin "14") (pinfunction "PA4_14") (pintype "bidirectional"))
    )
    (net (code "52") (name "TIM3_CH3") (class "Default")
      (node (ref "U6") (pin "10") (pinfunction "IN1_10") (pintype "input"))
      (node (ref "U7") (pin "18") (pinfunction "PB0_18") (pintype "bidirectional"))
    )
    (net (code "53") (name "TIM3_CH4") (class "Default")
      (node (ref "U6") (pin "8") (pinfunction "IN2_8") (pintype "input"))
      (node (ref "U7") (pin "19") (pinfunction "PB1_19") (pintype "bidirectional"))
    )
    (net (code "54") (name "USART1_RX") (class "Default")
      (node (ref "J6") (pin "1") (pinfunction "1_1") (pintype "bidirectional"))
      (node (ref "U4") (pin "26") (pinfunction "TXD_26") (pintype "output"))
      (node (ref "U7") (pin "31") (pinfunction "PA10_31") (pintype "bidirectional"))
    )
    (net (code "55") (name "USART1_TX") (class "Default")
      (node (ref "J6") (pin "2") (pinfunction "2_2") (pintype "bidirectional"))
      (node (ref "U4") (pin "25") (pinfunction "RXD_25") (pintype "input"))
      (node (ref "U7") (pin "30") (pinfunction "PA9_30") (pintype "bidirectional"))
    )
    (net (code "56") (name "VCC_MEASURE") (class "Default")
      (node (ref "R17") (pin "2") (pinfunction "22_2") (pintype "passive"))
      (node (ref "R18") (pin "1") (pinfunction "11_1") (pintype "passive"))
      (node (ref "U7") (pin "10") (pinfunction "PA0_10") (pintype "bidirectional"))
    )
    (net (code "57") (name "V_BATT") (class "Default")
      (node (ref "C1") (pin "2") (pinfunction "2_2") (pintype "bidirectional"))
      (node (ref "C13") (pin "2") (pinfunction "2_2") (pintype "bidirectional"))
      (node (ref "C18") (pin "2") (pinfunction "2_2") (pintype "bidirectional"))
      (node (ref "J3") (pin "1") (pinfunction "15V_1") (pintype "power_in"))
      (node (ref "R17") (pin "1") (pinfunction "11_1") (pintype "passive"))
      (node (ref "U1") (pin "12") (pinfunction "PVIN2_12") (pintype "input"))
      (node (ref "U1") (pin "13") (pinfunction "PVIN3_13") (pintype "input"))
      (node (ref "U1") (pin "28") (pinfunction "PVIN1_28") (pintype "input"))
      (node (ref "U1") (pin "29") (pinfunction "VIN_29") (pintype "input"))
    )
    (net (code "58") (name "unconnected-(J8-ID-Pad4)") (class "Default")
      (node (ref "J8") (pin "4") (pinfunction "ID_4") (pintype "bidirectional"))
    )
    (net (code "59") (name "unconnected-(U1-EN1-Pad31)") (class "Default")
      (node (ref "U1") (pin "31") (pinfunction "EN1_31") (pintype "input"))
    )
    (net (code "60") (name "unconnected-(U1-EN2-Pad32)") (class "Default")
      (node (ref "U1") (pin "32") (pinfunction "EN2_32") (pintype "input"))
    )
    (net (code "61") (name "unconnected-(U1-EN3-Pad1)") (class "Default")
      (node (ref "U1") (pin "1") (pinfunction "EN3_1") (pintype "input"))
    )
    (net (code "62") (name "unconnected-(U1-PGOOD-Pad2)") (class "Default")
      (node (ref "U1") (pin "2") (pinfunction "PGOOD_2") (pintype "output"))
    )
    (net (code "63") (name "unconnected-(U1-RESET-Pad3)") (class "Default")
      (node (ref "U1") (pin "3") (pinfunction "RESET_3") (pintype "output"))
    )
    (net (code "64") (name "unconnected-(U1-SS1-Pad24)") (class "Default")
      (node (ref "U1") (pin "24") (pinfunction "SS1_24") (pintype "input"))
    )
    (net (code "65") (name "unconnected-(U1-SS2-Pad8)") (class "Default")
      (node (ref "U1") (pin "8") (pinfunction "SS2_8") (pintype "input"))
    )
    (net (code "66") (name "unconnected-(U1-SS3-Pad17)") (class "Default")
      (node (ref "U1") (pin "17") (pinfunction "SS3_17") (pintype "input"))
    )
    (net (code "67") (name "unconnected-(U1-VDIV-Pad30)") (class "Default")
      (node (ref "U1") (pin "30") (pinfunction "VDIV_30") (pintype "input"))
    )
    (net (code "68") (name "unconnected-(U4-CTS-Pad23)") (class "Default")
      (node (ref "U4") (pin "23") (pinfunction "CTS_23") (pintype "input"))
    )
    (net (code "69") (name "unconnected-(U4-DCD-Pad1)") (class "Default")
      (node (ref "U4") (pin "1") (pinfunction "DCD_1") (pintype "input"))
    )
    (net (code "70") (name "unconnected-(U4-DSR-Pad27)") (class "Default")
      (node (ref "U4") (pin "27") (pinfunction "DSR_27") (pintype "input"))
    )
    (net (code "71") (name "unconnected-(U4-DTR-Pad28)") (class "Default")
      (node (ref "U4") (pin "28") (pinfunction "DTR_28") (pintype "output"))
    )
    (net (code "72") (name "unconnected-(U4-RI-Pad2)") (class "Default")
      (node (ref "U4") (pin "2") (pinfunction "RI_2") (pintype "input"))
    )
    (net (code "73") (name "unconnected-(U4-RTS-Pad24)") (class "Default")
      (node (ref "U4") (pin "24") (pinfunction "RTS_24") (pintype "output"))
    )
    (net (code "74") (name "unconnected-(U4-SUSPEND-Pad12)") (class "Default")
      (node (ref "U4") (pin "12") (pinfunction "SUSPEND_12") (pintype "output"))
    )
    (net (code "75") (name "unconnected-(U4-~{SUSPEND}-Pad11)") (class "Default")
      (node (ref "U4") (pin "11") (pinfunction "~{SUSPEND}_11") (pintype "output"))
    )
    (net (code "76") (name "unconnected-(U7-PA1-Pad11)") (class "Default")
      (node (ref "U7") (pin "11") (pinfunction "PA1_11") (pintype "bidirectional"))
    )
    (net (code "77") (name "unconnected-(U7-PA2-Pad12)") (class "Default")
      (node (ref "U7") (pin "12") (pinfunction "PA2_12") (pintype "bidirectional"))
    )
    (net (code "78") (name "unconnected-(U7-PA3-Pad13)") (class "Default")
      (node (ref "U7") (pin "13") (pinfunction "PA3_13") (pintype "bidirectional"))
    )
    (net (code "79") (name "unconnected-(U7-PA5-Pad15)") (class "Default")
      (node (ref "U7") (pin "15") (pinfunction "PA5_15") (pintype "bidirectional"))
    )
    (net (code "80") (name "unconnected-(U7-PA6-Pad16)") (class "Default")
      (node (ref "U7") (pin "16") (pinfunction "PA6_16") (pintype "bidirectional"))
    )
    (net (code "81") (name "unconnected-(U7-PA7-Pad17)") (class "Default")
      (node (ref "U7") (pin "17") (pinfunction "PA7_17") (pintype "bidirectional"))
    )
    (net (code "82") (name "unconnected-(U7-PA8-Pad29)") (class "Default")
      (node (ref "U7") (pin "29") (pinfunction "PA8_29") (pintype "bidirectional"))
    )
    (net (code "83") (name "unconnected-(U7-PA11-Pad32)") (class "Default")
      (node (ref "U7") (pin "32") (pinfunction "PA11_32") (pintype "bidirectional"))
    )
    (net (code "84") (name "unconnected-(U7-PA12-Pad33)") (class "Default")
      (node (ref "U7") (pin "33") (pinfunction "PA12_33") (pintype "bidirectional"))
    )
    (net (code "85") (name "unconnected-(U7-PA13-Pad34)") (class "Default")
      (node (ref "U7") (pin "34") (pinfunction "PA13_34") (pintype "bidirectional"))
    )
    (net (code "86") (name "unconnected-(U7-PB2-Pad20)") (class "Default")
      (node (ref "U7") (pin "20") (pinfunction "PB2_20") (pintype "bidirectional"))
    )
    (net (code "87") (name "unconnected-(U7-PB3-Pad39)") (class "Default")
      (node (ref "U7") (pin "39") (pinfunction "PB3_39") (pintype "bidirectional"))
    )
    (net (code "88") (name "unconnected-(U7-PB4-Pad40)") (class "Default")
      (node (ref "U7") (pin "40") (pinfunction "PB4_40") (pintype "bidirectional"))
    )
    (net (code "89") (name "unconnected-(U7-PB8-Pad45)") (class "Default")
      (node (ref "U7") (pin "45") (pinfunction "PB8_45") (pintype "bidirectional"))
    )
    (net (code "90") (name "unconnected-(U7-PB9-Pad46)") (class "Default")
      (node (ref "U7") (pin "46") (pinfunction "PB9_46") (pintype "bidirectional"))
    )
    (net (code "91") (name "unconnected-(U7-PB11-Pad22)") (class "Default")
      (node (ref "U7") (pin "22") (pinfunction "PB11_22") (pintype "bidirectional"))
    )
    (net (code "92") (name "unconnected-(U7-PC14-Pad3)") (class "Default")
      (node (ref "U7") (pin "3") (pinfunction "PC14_3") (pintype "bidirectional"))
    )
    (net (code "93") (name "unconnected-(U7-PC15-Pad4)") (class "Default")
      (node (ref "U7") (pin "4") (pinfunction "PC15_4") (pintype "bidirectional"))
    )
  )
)
